# automotive-mirror-communication-pin-term.net
KiCad netlist of a schematic drawn in Altium Designer
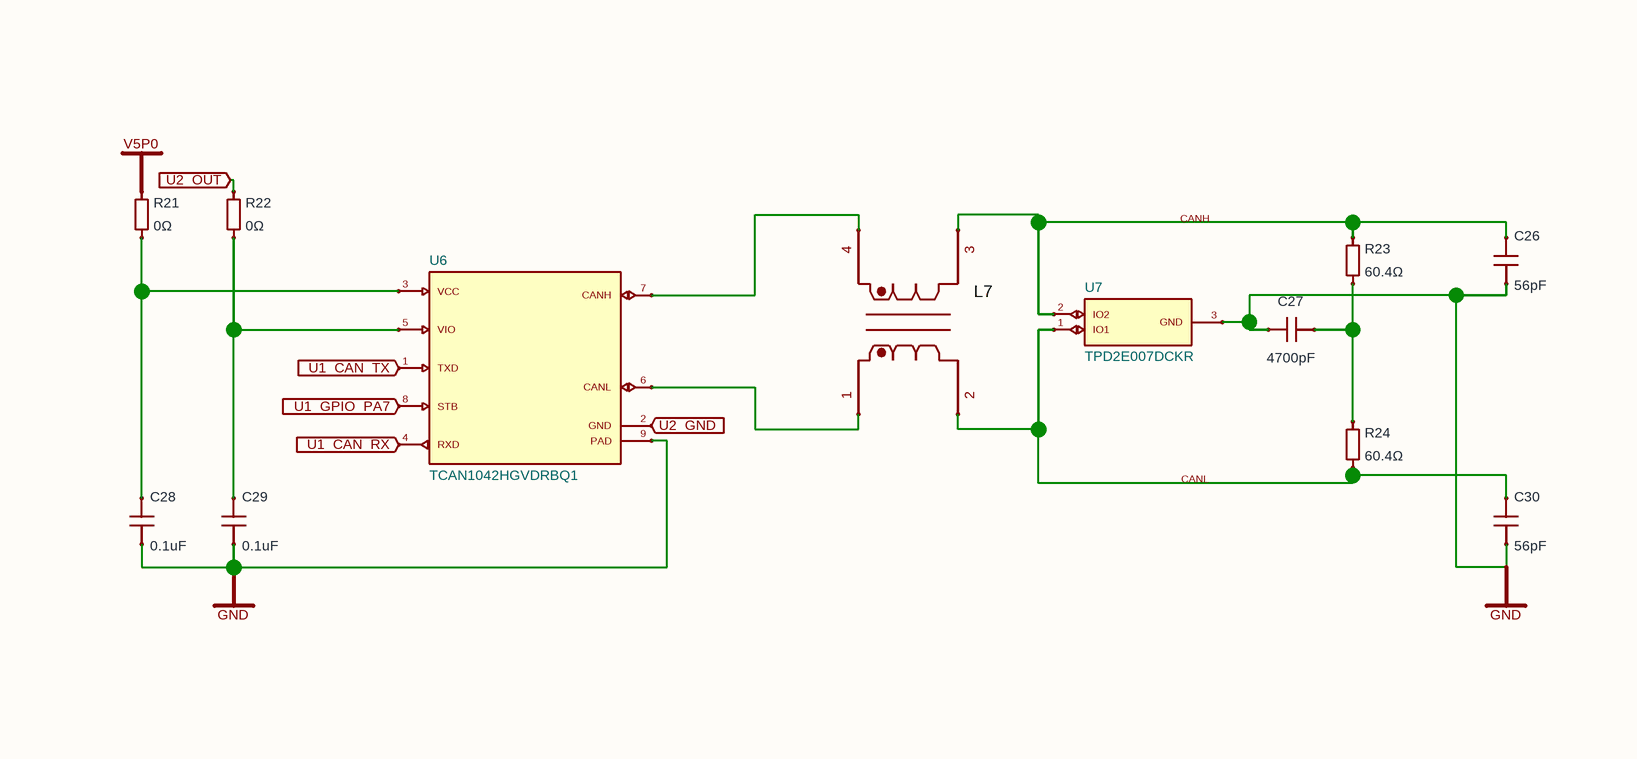
[diagram p0: automotive-mirror-communication-pin-terminals.SchDoc]

(export (version "E")
  (design (tool "Eeschema 10.0.6"))
  (components
    (comp (ref "C26") (value "56pF") (libsource (lib "altium-import") (part "root_0_capacitor_down_")))
    (comp (ref "C27") (value "4700pF") (libsource (lib "altium-import") (part "root_0_capacitor_right_")))
    (comp (ref "C28") (value "0.1uF") (libsource (lib "altium-import") (part "root_0_capacitor_down_")))
    (comp (ref "C29") (value "0.1uF") (libsource (lib "altium-import") (part "root_0_capacitor_down_")))
    (comp (ref "C30") (value "56pF") (libsource (lib "altium-import") (part "root_0_capacitor_down_")))
    (comp (ref "L7") (value "~") (libsource (lib "altium-import") (part "root_0_L7_")))
    (comp (ref "R21") (value "0Ω") (libsource (lib "altium-import") (part "root_0_boxresistor_down_")))
    (comp (ref "R22") (value "0Ω") (libsource (lib "altium-import") (part "root_0_boxresistor_down_")))
    (comp (ref "R23") (value "60.4Ω") (libsource (lib "altium-import") (part "root_0_boxresistor_down_")))
    (comp (ref "R24") (value "60.4Ω") (libsource (lib "altium-import") (part "root_0_boxresistor_down_")))
    (comp (ref "U6") (value "~") (libsource (lib "altium-import") (part "root_0_U6_")))
    (comp (ref "U7") (value "~") (libsource (lib "altium-import") (part "root_0_U7_")))
  )
  (nets
    (net (code "1") (name "/U1_CAN_RX") (class "Default")
      (node (ref "U6") (pin "4") (pinfunction "RXD_4") (pintype "passive"))
    )
    (net (code "2") (name "/U1_CAN_TX") (class "Default")
      (node (ref "U6") (pin "1") (pinfunction "TXD_1") (pintype "passive"))
    )
    (net (code "3") (name "/U1_GPIO_PA7") (class "Default")
      (node (ref "U6") (pin "8") (pinfunction "STB_8") (pintype "passive"))
    )
    (net (code "4") (name "/U2_GND") (class "Default")
      (node (ref "U6") (pin "2") (pinfunction "GND_2") (pintype "passive"))
    )
    (net (code "5") (name "/U2_OUT") (class "Default")
      (node (ref "R22") (pin "1") (pinfunction "anode_1") (pintype "passive"))
    )
    (net (code "6") (name "GND") (class "Default")
      (node (ref "C26") (pin "2") (pinfunction "cathode_2") (pintype "passive"))
      (node (ref "C27") (pin "1") (pinfunction "pos_1") (pintype "passive"))
      (node (ref "C28") (pin "2") (pinfunction "cathode_2") (pintype "passive"))
      (node (ref "C29") (pin "2") (pinfunction "cathode_2") (pintype "passive"))
      (node (ref "C30") (pin "2") (pinfunction "cathode_2") (pintype "passive"))
      (node (ref "U6") (pin "9") (pinfunction "PAD_9") (pintype "passive"))
      (node (ref "U7") (pin "3") (pinfunction "GND_3") (pintype "passive"))
    )
    (net (code "7") (name "Net-(C26-anode)") (class "Default")
      (node (ref "C26") (pin "1") (pinfunction "anode_1") (pintype "passive"))
      (node (ref "L7") (pin "3") (pinfunction "pin3_3") (pintype "passive"))
      (node (ref "R23") (pin "1") (pinfunction "anode_1") (pintype "passive"))
      (node (ref "U7") (pin "2") (pinfunction "IO2_2") (pintype "passive"))
    )
    (net (code "8") (name "Net-(C27-neg)") (class "Default")
      (node (ref "C27") (pin "2") (pinfunction "neg_2") (pintype "passive"))
      (node (ref "R23") (pin "2") (pinfunction "cathode_2") (pintype "passive"))
      (node (ref "R24") (pin "1") (pinfunction "anode_1") (pintype "passive"))
    )
    (net (code "9") (name "Net-(C28-anode)") (class "Default")
      (node (ref "C28") (pin "1") (pinfunction "anode_1") (pintype "passive"))
      (node (ref "R21") (pin "2") (pinfunction "cathode_2") (pintype "passive"))
      (node (ref "U6") (pin "3") (pinfunction "VCC_3") (pintype "passive"))
    )
    (net (code "10") (name "Net-(C29-anode)") (class "Default")
      (node (ref "C29") (pin "1") (pinfunction "anode_1") (pintype "passive"))
      (node (ref "R22") (pin "2") (pinfunction "cathode_2") (pintype "passive"))
      (node (ref "U6") (pin "5") (pinfunction "VIO_5") (pintype "passive"))
    )
    (net (code "11") (name "Net-(C30-anode)") (class "Default")
      (node (ref "C30") (pin "1") (pinfunction "anode_1") (pintype "passive"))
      (node (ref "L7") (pin "2") (pinfunction "pin2_2") (pintype "passive"))
      (node (ref "R24") (pin "2") (pinfunction "cathode_2") (pintype "passive"))
      (node (ref "U7") (pin "1") (pinfunction "IO1_1") (pintype "passive"))
    )
    (net (code "12") (name "Net-(L7-pin1)") (class "Default")
      (node (ref "L7") (pin "1") (pinfunction "pin1_1") (pintype "passive"))
      (node (ref "U6") (pin "6") (pinfunction "CANL_6") (pintype "passive"))
    )
    (net (code "13") (name "Net-(L7-pin4)") (class "Default")
      (node (ref "L7") (pin "4") (pinfunction "pin4_4") (pintype "passive"))
      (node (ref "U6") (pin "7") (pinfunction "CANH_7") (pintype "passive"))
    )
    (net (code "14") (name "V5P0") (class "Default")
      (node (ref "R21") (pin "1") (pinfunction "anode_1") (pintype "passive"))
    )
  )
)
